# pcie_rs485.net
KiCad netlist of a schematic drawn in EAGLE
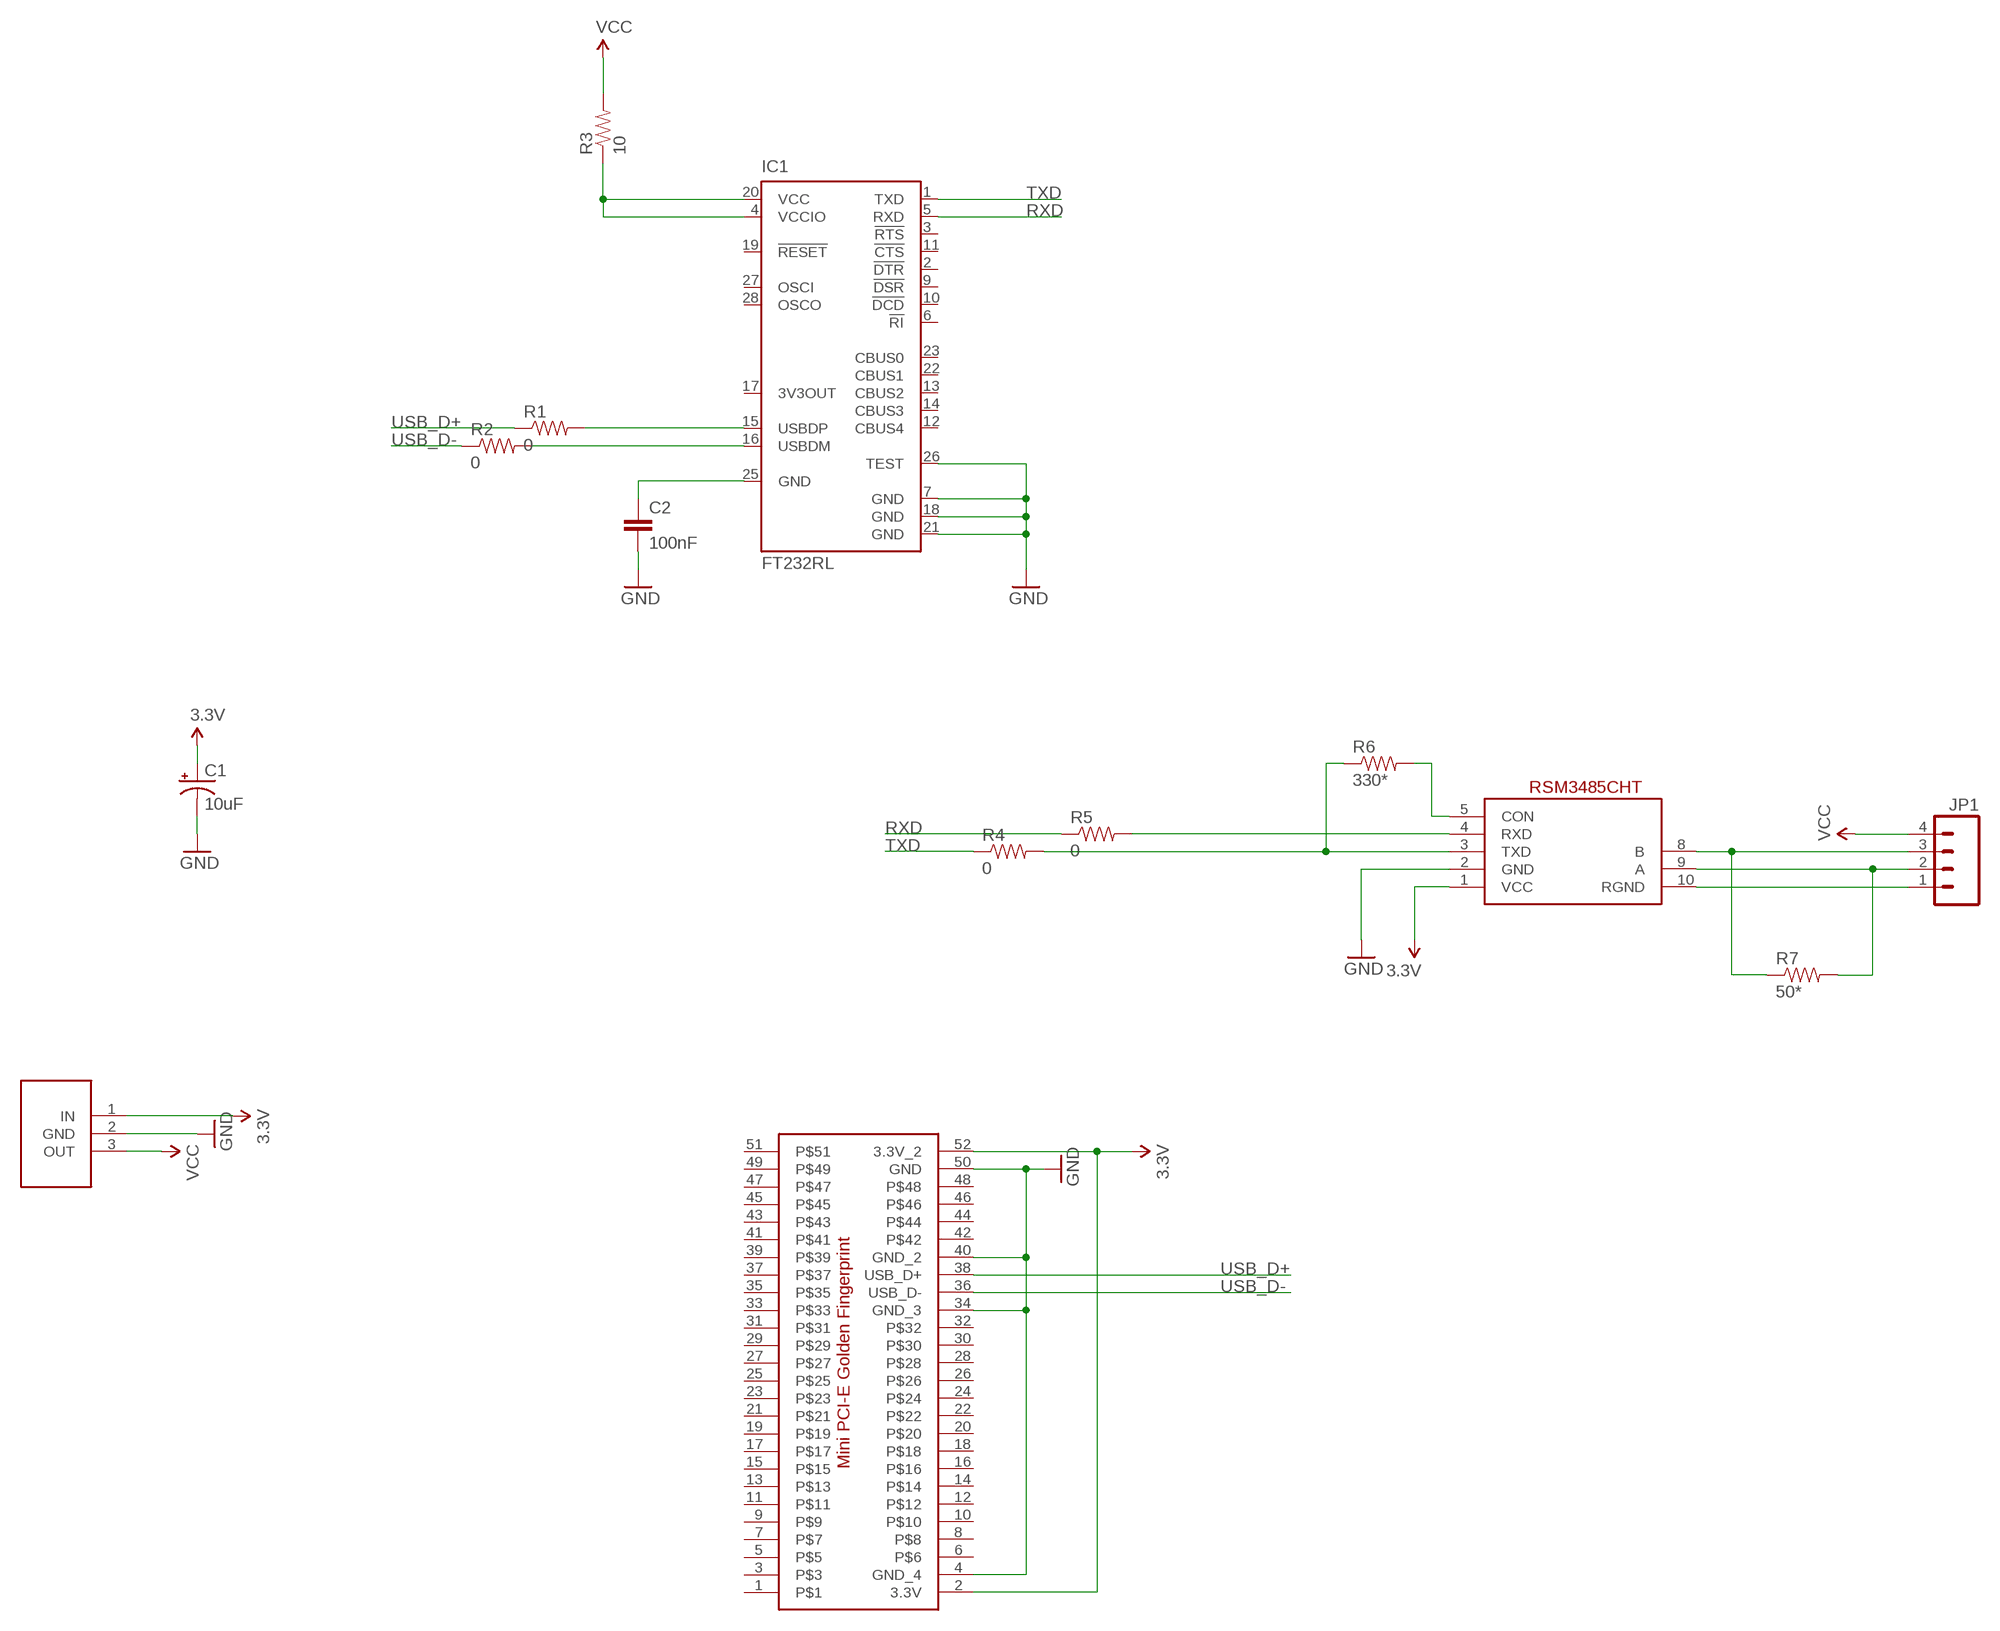
[diagram p0: schematic, sheet 1]

(export (version "E")
  (design (tool "Eeschema 10.0.6"))
  (components
    (comp (ref "C1")
      (value "10uF")
      (footprint "eagle-import:EIA3216")
      (libsource (lib "eagle-import") (part "CAP_POL1206"))
    )
    (comp (ref "C2")
      (value "100nF")
      (footprint "eagle-import:0603-CAP")
      (libsource (lib "eagle-import") (part "0.1UF-25V(+80/-20%)(0603)"))
    )
    (comp (ref "IC1")
      (value "FT232RL")
      (footprint "eagle-import:SSOP28")
      (libsource (lib "eagle-import") (part "FT232RL"))
    )
    (comp (ref "JP1")
      (value "M04PTH")
      (footprint "eagle-import:1X04")
      (libsource (lib "eagle-import") (part "M04PTH"))
    )
    (comp (ref "NC1")
      (value "RSM3485CHT")
      (footprint "eagle-import:RSM3485CHT")
      (libsource (lib "eagle-import") (part "RSM3485CHT"))
    )
    (comp (ref "R1")
      (value "0")
      (footprint "eagle-import:0603-RES")
      (libsource (lib "eagle-import") (part "330OHM1/10W1%(0603)"))
    )
    (comp (ref "R2")
      (value "0")
      (footprint "eagle-import:0603-RES")
      (libsource (lib "eagle-import") (part "330OHM1/10W1%(0603)"))
    )
    (comp (ref "R3")
      (value "10")
      (footprint "eagle-import:0603-RES")
      (libsource (lib "eagle-import") (part "330OHM1/10W1%(0603)"))
    )
    (comp (ref "R4")
      (value "0")
      (footprint "eagle-import:0603-RES")
      (libsource (lib "eagle-import") (part "330OHM1/10W1%(0603)"))
    )
    (comp (ref "R5")
      (value "0")
      (footprint "eagle-import:0603-RES")
      (libsource (lib "eagle-import") (part "330OHM1/10W1%(0603)"))
    )
    (comp (ref "R6")
      (value "330*")
      (footprint "eagle-import:0603-RES")
      (libsource (lib "eagle-import") (part "330OHM1/10W1%(0603)"))
    )
    (comp (ref "R7")
      (value "50*")
      (footprint "eagle-import:0603-RES")
      (libsource (lib "eagle-import") (part "330OHM1/10W1%(0603)"))
    )
    (comp (ref "U1")
      (value "MINI_PCIE_MODULE")
      (footprint "eagle-import:MINI_PCIE")
      (libsource (lib "eagle-import") (part "MINI_PCIE_MODULE"))
    )
    (comp (ref "U?1")
      (value "BL8530_M_V5.0")
      (footprint "eagle-import:BL8530_M")
      (libsource (lib "eagle-import") (part "BL8530_M_V5.0"))
    )
  )
  (nets
    (net (code "1") (name "/RXD") (class "Default")
      (node (ref "IC1") (pin "5") (pinfunction "RXD_5") (pintype "input"))
      (node (ref "R5") (pin "1") (pinfunction "1_1") (pintype "passive"))
    )
    (net (code "2") (name "/TXD") (class "Default")
      (node (ref "IC1") (pin "1") (pinfunction "TXD_1") (pintype "output"))
      (node (ref "R4") (pin "1") (pinfunction "1_1") (pintype "passive"))
    )
    (net (code "3") (name "/USB_D+") (class "Default")
      (node (ref "R1") (pin "1") (pinfunction "1_1") (pintype "passive"))
      (node (ref "U1") (pin "38") (pinfunction "USB_D+_38") (pintype "bidirectional"))
    )
    (net (code "4") (name "/USB_D-") (class "Default")
      (node (ref "R2") (pin "1") (pinfunction "1_1") (pintype "passive"))
      (node (ref "U1") (pin "36") (pinfunction "USB_D-_36") (pintype "bidirectional"))
    )
    (net (code "5") (name "3.3V") (class "Default")
      (node (ref "C1") (pin "A") (pinfunction "+_A") (pintype "passive"))
      (node (ref "NC1") (pin "1") (pinfunction "VCC_1") (pintype "bidirectional"))
      (node (ref "U1") (pin "2") (pinfunction "3.3V_2") (pintype "bidirectional"))
      (node (ref "U1") (pin "52") (pinfunction "3.3V_2_52") (pintype "bidirectional"))
      (node (ref "U?1") (pin "1") (pinfunction "IN_1") (pintype "bidirectional"))
    )
    (net (code "6") (name "GND") (class "Default")
      (node (ref "C1") (pin "C") (pinfunction "-_C") (pintype "passive"))
      (node (ref "C2") (pin "2") (pinfunction "2_2") (pintype "passive"))
      (node (ref "IC1") (pin "18") (pinfunction "GND_18") (pintype "power_in"))
      (node (ref "IC1") (pin "21") (pinfunction "GND_21") (pintype "power_in"))
      (node (ref "IC1") (pin "26") (pinfunction "TEST_26") (pintype "input"))
      (node (ref "IC1") (pin "7") (pinfunction "GND_7") (pintype "power_in"))
      (node (ref "NC1") (pin "2") (pinfunction "GND_2") (pintype "bidirectional"))
      (node (ref "U1") (pin "34") (pinfunction "GND_3_34") (pintype "bidirectional"))
      (node (ref "U1") (pin "4") (pinfunction "GND_4_4") (pintype "bidirectional"))
      (node (ref "U1") (pin "40") (pinfunction "GND_2_40") (pintype "bidirectional"))
      (node (ref "U1") (pin "50") (pinfunction "GND_50") (pintype "bidirectional"))
      (node (ref "U?1") (pin "2") (pinfunction "GND_2") (pintype "bidirectional"))
    )
    (net (code "7") (name "Net-(C2-Pad1)") (class "Default")
      (node (ref "C2") (pin "1") (pinfunction "1_1") (pintype "passive"))
      (node (ref "IC1") (pin "25") (pinfunction "GND_25") (pintype "power_in"))
    )
    (net (code "8") (name "Net-(IC1-USBDM)") (class "Default")
      (node (ref "IC1") (pin "16") (pinfunction "USBDM_16") (pintype "bidirectional"))
      (node (ref "R2") (pin "2") (pinfunction "2_2") (pintype "passive"))
    )
    (net (code "9") (name "Net-(IC1-USBDP)") (class "Default")
      (node (ref "IC1") (pin "15") (pinfunction "USBDP_15") (pintype "bidirectional"))
      (node (ref "R1") (pin "2") (pinfunction "2_2") (pintype "passive"))
    )
    (net (code "10") (name "Net-(IC1-VCC)") (class "Default")
      (node (ref "IC1") (pin "20") (pinfunction "VCC_20") (pintype "power_in"))
      (node (ref "IC1") (pin "4") (pinfunction "VCCIO_4") (pintype "power_in"))
      (node (ref "R3") (pin "1") (pinfunction "1_1") (pintype "passive"))
    )
    (net (code "11") (name "Net-(NC1-A)") (class "Default")
      (node (ref "JP1") (pin "2") (pinfunction "2_2") (pintype "passive"))
      (node (ref "NC1") (pin "9") (pinfunction "A_9") (pintype "bidirectional"))
      (node (ref "R7") (pin "2") (pinfunction "2_2") (pintype "passive"))
    )
    (net (code "12") (name "Net-(NC1-B)") (class "Default")
      (node (ref "JP1") (pin "3") (pinfunction "3_3") (pintype "passive"))
      (node (ref "NC1") (pin "8") (pinfunction "B_8") (pintype "bidirectional"))
      (node (ref "R7") (pin "1") (pinfunction "1_1") (pintype "passive"))
    )
    (net (code "13") (name "Net-(NC1-CON)") (class "Default")
      (node (ref "NC1") (pin "5") (pinfunction "CON_5") (pintype "bidirectional"))
      (node (ref "R6") (pin "2") (pinfunction "2_2") (pintype "passive"))
    )
    (net (code "14") (name "Net-(NC1-RGND)") (class "Default")
      (node (ref "JP1") (pin "1") (pinfunction "1_1") (pintype "passive"))
      (node (ref "NC1") (pin "10") (pinfunction "RGND_10") (pintype "bidirectional"))
    )
    (net (code "15") (name "Net-(NC1-RXD)") (class "Default")
      (node (ref "NC1") (pin "4") (pinfunction "RXD_4") (pintype "bidirectional"))
      (node (ref "R5") (pin "2") (pinfunction "2_2") (pintype "passive"))
    )
    (net (code "16") (name "Net-(NC1-TXD)") (class "Default")
      (node (ref "NC1") (pin "3") (pinfunction "TXD_3") (pintype "bidirectional"))
      (node (ref "R4") (pin "2") (pinfunction "2_2") (pintype "passive"))
      (node (ref "R6") (pin "1") (pinfunction "1_1") (pintype "passive"))
    )
    (net (code "17") (name "VCC") (class "Default")
      (node (ref "JP1") (pin "4") (pinfunction "4_4") (pintype "passive"))
      (node (ref "R3") (pin "2") (pinfunction "2_2") (pintype "passive"))
      (node (ref "U?1") (pin "3") (pinfunction "OUT_3") (pintype "bidirectional"))
    )
    (net (code "18") (name "unconnected-(IC1-3V3OUT-Pad17)") (class "Default")
      (node (ref "IC1") (pin "17") (pinfunction "3V3OUT_17") (pintype "output"))
    )
    (net (code "19") (name "unconnected-(IC1-CBUS0-Pad23)") (class "Default")
      (node (ref "IC1") (pin "23") (pinfunction "CBUS0_23") (pintype "bidirectional"))
    )
    (net (code "20") (name "unconnected-(IC1-CBUS1-Pad22)") (class "Default")
      (node (ref "IC1") (pin "22") (pinfunction "CBUS1_22") (pintype "bidirectional"))
    )
    (net (code "21") (name "unconnected-(IC1-CBUS2-Pad13)") (class "Default")
      (node (ref "IC1") (pin "13") (pinfunction "CBUS2_13") (pintype "bidirectional"))
    )
    (net (code "22") (name "unconnected-(IC1-CBUS3-Pad14)") (class "Default")
      (node (ref "IC1") (pin "14") (pinfunction "CBUS3_14") (pintype "bidirectional"))
    )
    (net (code "23") (name "unconnected-(IC1-CBUS4-Pad12)") (class "Default")
      (node (ref "IC1") (pin "12") (pinfunction "CBUS4_12") (pintype "bidirectional"))
    )
    (net (code "24") (name "unconnected-(IC1-OSCI-Pad27)") (class "Default")
      (node (ref "IC1") (pin "27") (pinfunction "OSCI_27") (pintype "input"))
    )
    (net (code "25") (name "unconnected-(IC1-OSCO-Pad28)") (class "Default")
      (node (ref "IC1") (pin "28") (pinfunction "OSCO_28") (pintype "output"))
    )
    (net (code "26") (name "unconnected-(IC1-~{CTS}-Pad11)") (class "Default")
      (node (ref "IC1") (pin "11") (pinfunction "~{CTS}_11") (pintype "input"))
    )
    (net (code "27") (name "unconnected-(IC1-~{DCD}-Pad10)") (class "Default")
      (node (ref "IC1") (pin "10") (pinfunction "~{DCD}_10") (pintype "input"))
    )
    (net (code "28") (name "unconnected-(IC1-~{DSR}-Pad9)") (class "Default")
      (node (ref "IC1") (pin "9") (pinfunction "~{DSR}_9") (pintype "input"))
    )
    (net (code "29") (name "unconnected-(IC1-~{DTR}-Pad2)") (class "Default")
      (node (ref "IC1") (pin "2") (pinfunction "~{DTR}_2") (pintype "output"))
    )
    (net (code "30") (name "unconnected-(IC1-~{RESET}-Pad19)") (class "Default")
      (node (ref "IC1") (pin "19") (pinfunction "~{RESET}_19") (pintype "input"))
    )
    (net (code "31") (name "unconnected-(IC1-~{RI}-Pad6)") (class "Default")
      (node (ref "IC1") (pin "6") (pinfunction "~{RI}_6") (pintype "input"))
    )
    (net (code "32") (name "unconnected-(IC1-~{RTS}-Pad3)") (class "Default")
      (node (ref "IC1") (pin "3") (pinfunction "~{RTS}_3") (pintype "output"))
    )
    (net (code "33") (name "unconnected-(U1-P$1-Pad1)") (class "Default")
      (node (ref "U1") (pin "1") (pinfunction "P$1_1") (pintype "bidirectional"))
    )
    (net (code "34") (name "unconnected-(U1-P$3-Pad3)") (class "Default")
      (node (ref "U1") (pin "3") (pinfunction "P$3_3") (pintype "bidirectional"))
    )
    (net (code "35") (name "unconnected-(U1-P$5-Pad5)") (class "Default")
      (node (ref "U1") (pin "5") (pinfunction "P$5_5") (pintype "bidirectional"))
    )
    (net (code "36") (name "unconnected-(U1-P$6-Pad6)") (class "Default")
      (node (ref "U1") (pin "6") (pinfunction "P$6_6") (pintype "bidirectional"))
    )
    (net (code "37") (name "unconnected-(U1-P$7-Pad7)") (class "Default")
      (node (ref "U1") (pin "7") (pinfunction "P$7_7") (pintype "bidirectional"))
    )
    (net (code "38") (name "unconnected-(U1-P$8-Pad8)") (class "Default")
      (node (ref "U1") (pin "8") (pinfunction "P$8_8") (pintype "bidirectional"))
    )
    (net (code "39") (name "unconnected-(U1-P$9-Pad9)") (class "Default")
      (node (ref "U1") (pin "9") (pinfunction "P$9_9") (pintype "bidirectional"))
    )
    (net (code "40") (name "unconnected-(U1-P$10-Pad10)") (class "Default")
      (node (ref "U1") (pin "10") (pinfunction "P$10_10") (pintype "bidirectional"))
    )
    (net (code "41") (name "unconnected-(U1-P$11-Pad11)") (class "Default")
      (node (ref "U1") (pin "11") (pinfunction "P$11_11") (pintype "bidirectional"))
    )
    (net (code "42") (name "unconnected-(U1-P$12-Pad12)") (class "Default")
      (node (ref "U1") (pin "12") (pinfunction "P$12_12") (pintype "bidirectional"))
    )
    (net (code "43") (name "unconnected-(U1-P$13-Pad13)") (class "Default")
      (node (ref "U1") (pin "13") (pinfunction "P$13_13") (pintype "bidirectional"))
    )
    (net (code "44") (name "unconnected-(U1-P$14-Pad14)") (class "Default")
      (node (ref "U1") (pin "14") (pinfunction "P$14_14") (pintype "bidirectional"))
    )
    (net (code "45") (name "unconnected-(U1-P$15-Pad15)") (class "Default")
      (node (ref "U1") (pin "15") (pinfunction "P$15_15") (pintype "bidirectional"))
    )
    (net (code "46") (name "unconnected-(U1-P$16-Pad16)") (class "Default")
      (node (ref "U1") (pin "16") (pinfunction "P$16_16") (pintype "bidirectional"))
    )
    (net (code "47") (name "unconnected-(U1-P$17-Pad17)") (class "Default")
      (node (ref "U1") (pin "17") (pinfunction "P$17_17") (pintype "bidirectional"))
    )
    (net (code "48") (name "unconnected-(U1-P$18-Pad18)") (class "Default")
      (node (ref "U1") (pin "18") (pinfunction "P$18_18") (pintype "bidirectional"))
    )
    (net (code "49") (name "unconnected-(U1-P$19-Pad19)") (class "Default")
      (node (ref "U1") (pin "19") (pinfunction "P$19_19") (pintype "bidirectional"))
    )
    (net (code "50") (name "unconnected-(U1-P$20-Pad20)") (class "Default")
      (node (ref "U1") (pin "20") (pinfunction "P$20_20") (pintype "bidirectional"))
    )
    (net (code "51") (name "unconnected-(U1-P$21-Pad21)") (class "Default")
      (node (ref "U1") (pin "21") (pinfunction "P$21_21") (pintype "bidirectional"))
    )
    (net (code "52") (name "unconnected-(U1-P$22-Pad22)") (class "Default")
      (node (ref "U1") (pin "22") (pinfunction "P$22_22") (pintype "bidirectional"))
    )
    (net (code "53") (name "unconnected-(U1-P$23-Pad23)") (class "Default")
      (node (ref "U1") (pin "23") (pinfunction "P$23_23") (pintype "bidirectional"))
    )
    (net (code "54") (name "unconnected-(U1-P$24-Pad24)") (class "Default")
      (node (ref "U1") (pin "24") (pinfunction "P$24_24") (pintype "bidirectional"))
    )
    (net (code "55") (name "unconnected-(U1-P$25-Pad25)") (class "Default")
      (node (ref "U1") (pin "25") (pinfunction "P$25_25") (pintype "bidirectional"))
    )
    (net (code "56") (name "unconnected-(U1-P$26-Pad26)") (class "Default")
      (node (ref "U1") (pin "26") (pinfunction "P$26_26") (pintype "bidirectional"))
    )
    (net (code "57") (name "unconnected-(U1-P$27-Pad27)") (class "Default")
      (node (ref "U1") (pin "27") (pinfunction "P$27_27") (pintype "bidirectional"))
    )
    (net (code "58") (name "unconnected-(U1-P$28-Pad28)") (class "Default")
      (node (ref "U1") (pin "28") (pinfunction "P$28_28") (pintype "bidirectional"))
    )
    (net (code "59") (name "unconnected-(U1-P$29-Pad29)") (class "Default")
      (node (ref "U1") (pin "29") (pinfunction "P$29_29") (pintype "bidirectional"))
    )
    (net (code "60") (name "unconnected-(U1-P$30-Pad30)") (class "Default")
      (node (ref "U1") (pin "30") (pinfunction "P$30_30") (pintype "bidirectional"))
    )
    (net (code "61") (name "unconnected-(U1-P$31-Pad31)") (class "Default")
      (node (ref "U1") (pin "31") (pinfunction "P$31_31") (pintype "bidirectional"))
    )
    (net (code "62") (name "unconnected-(U1-P$32-Pad32)") (class "Default")
      (node (ref "U1") (pin "32") (pinfunction "P$32_32") (pintype "bidirectional"))
    )
    (net (code "63") (name "unconnected-(U1-P$33-Pad33)") (class "Default")
      (node (ref "U1") (pin "33") (pinfunction "P$33_33") (pintype "bidirectional"))
    )
    (net (code "64") (name "unconnected-(U1-P$35-Pad35)") (class "Default")
      (node (ref "U1") (pin "35") (pinfunction "P$35_35") (pintype "bidirectional"))
    )
    (net (code "65") (name "unconnected-(U1-P$37-Pad37)") (class "Default")
      (node (ref "U1") (pin "37") (pinfunction "P$37_37") (pintype "bidirectional"))
    )
    (net (code "66") (name "unconnected-(U1-P$39-Pad39)") (class "Default")
      (node (ref "U1") (pin "39") (pinfunction "P$39_39") (pintype "bidirectional"))
    )
    (net (code "67") (name "unconnected-(U1-P$41-Pad41)") (class "Default")
      (node (ref "U1") (pin "41") (pinfunction "P$41_41") (pintype "bidirectional"))
    )
    (net (code "68") (name "unconnected-(U1-P$42-Pad42)") (class "Default")
      (node (ref "U1") (pin "42") (pinfunction "P$42_42") (pintype "bidirectional"))
    )
    (net (code "69") (name "unconnected-(U1-P$43-Pad43)") (class "Default")
      (node (ref "U1") (pin "43") (pinfunction "P$43_43") (pintype "bidirectional"))
    )
    (net (code "70") (name "unconnected-(U1-P$44-Pad44)") (class "Default")
      (node (ref "U1") (pin "44") (pinfunction "P$44_44") (pintype "bidirectional"))
    )
    (net (code "71") (name "unconnected-(U1-P$45-Pad45)") (class "Default")
      (node (ref "U1") (pin "45") (pinfunction "P$45_45") (pintype "bidirectional"))
    )
    (net (code "72") (name "unconnected-(U1-P$46-Pad46)") (class "Default")
      (node (ref "U1") (pin "46") (pinfunction "P$46_46") (pintype "bidirectional"))
    )
    (net (code "73") (name "unconnected-(U1-P$47-Pad47)") (class "Default")
      (node (ref "U1") (pin "47") (pinfunction "P$47_47") (pintype "bidirectional"))
    )
    (net (code "74") (name "unconnected-(U1-P$48-Pad48)") (class "Default")
      (node (ref "U1") (pin "48") (pinfunction "P$48_48") (pintype "bidirectional"))
    )
    (net (code "75") (name "unconnected-(U1-P$49-Pad49)") (class "Default")
      (node (ref "U1") (pin "49") (pinfunction "P$49_49") (pintype "bidirectional"))
    )
    (net (code "76") (name "unconnected-(U1-P$51-Pad51)") (class "Default")
      (node (ref "U1") (pin "51") (pinfunction "P$51_51") (pintype "bidirectional"))
    )
  )
)
